# LoRa.net
KiCad netlist of a schematic drawn in Altium Designer
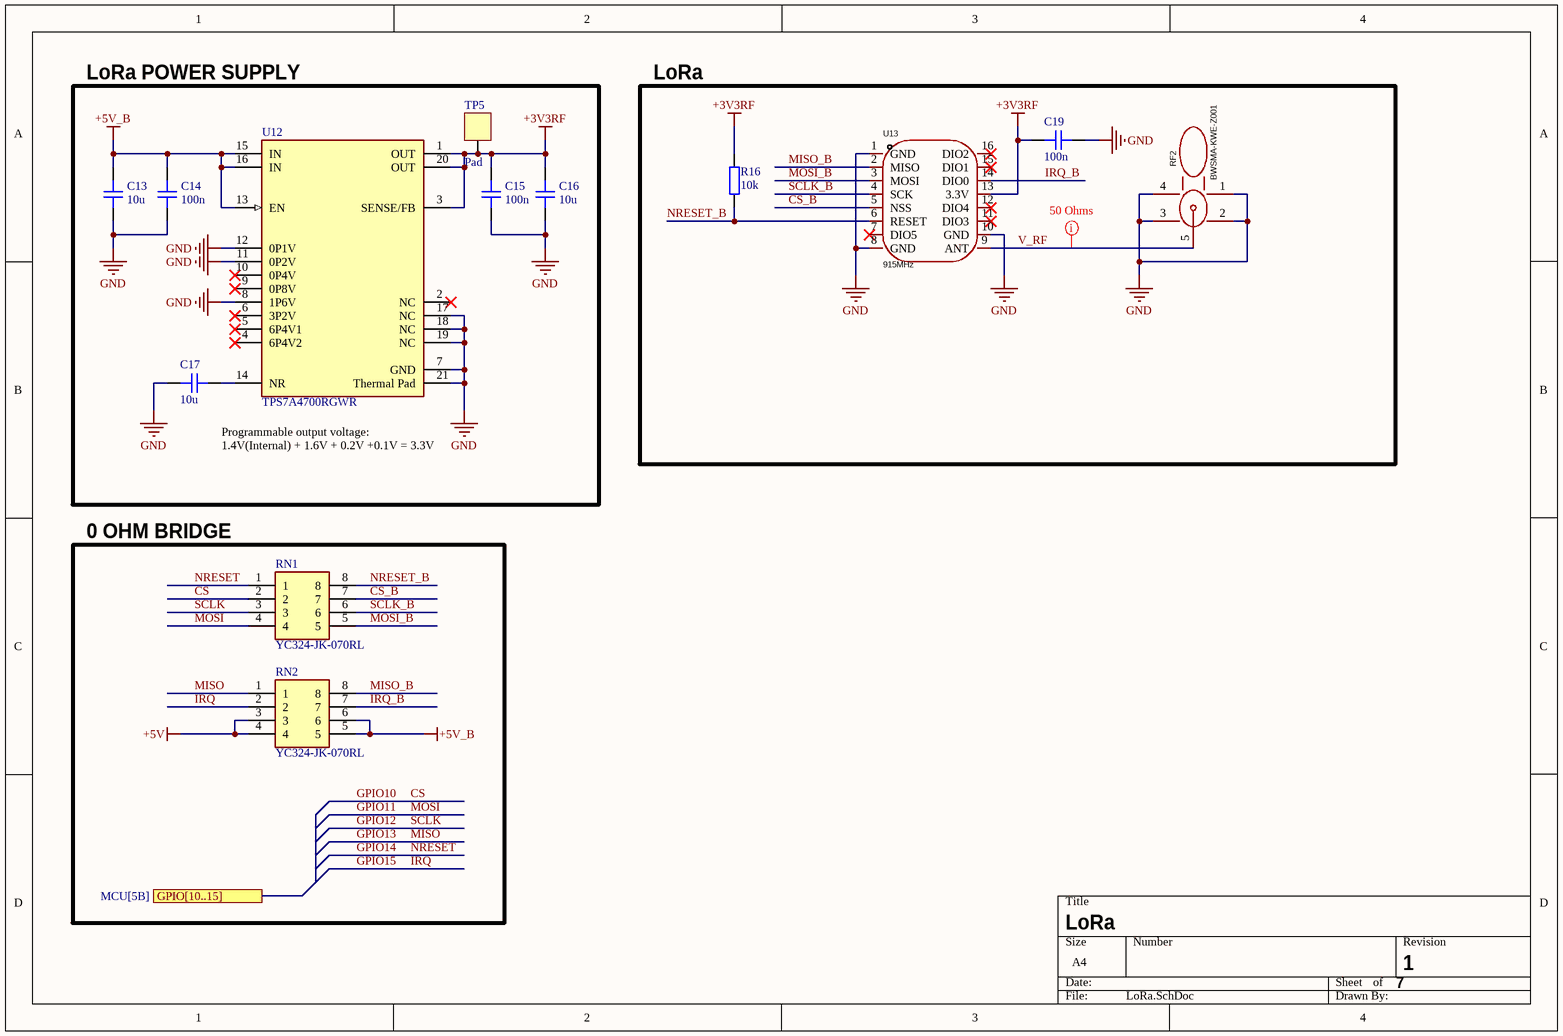
[diagram p0: LoRa.SchDoc]

(export (version "E")
  (design (tool "Eeschema 10.0.6"))
  (components
    (comp (ref "C13")
      (value "10u")
      (footprint "CAP_0402")
      (description "Capacitor SMD 0402")
      (fields (field (name "Comment") "CL05A106MQ5NUNC"))
      (libsource (lib "Schematic-Lib-PhilsLab") (part "CAP_0402"))
    )
    (comp (ref "C14")
      (value "CL05B104KB54PNC")
      (footprint "CAP_0402")
      (description "Capacitor SMD 0402")
      (fields (field (name "RATING") "100n"))
      (libsource (lib "Schematic-Lib-PhilsLab") (part "CAP_0402"))
    )
    (comp (ref "C15")
      (value "CL05B104KB54PNC")
      (footprint "CAP_0402")
      (description "Capacitor SMD 0402")
      (fields (field (name "RATING") "100n"))
      (libsource (lib "Schematic-Lib-PhilsLab") (part "CAP_0402"))
    )
    (comp (ref "C16")
      (value "10u")
      (footprint "CAP_0402")
      (description "Capacitor SMD 0402")
      (fields (field (name "Comment") "CL05A106MQ5NUNC"))
      (libsource (lib "Schematic-Lib-PhilsLab") (part "CAP_0402"))
    )
    (comp (ref "C17")
      (value "10u")
      (footprint "CAP_0402")
      (description "Capacitor SMD 0402")
      (fields (field (name "Comment") "CL05A106MQ5NUNC"))
      (libsource (lib "Schematic-Lib-PhilsLab") (part "CAP_0402"))
    )
    (comp (ref "C19")
      (value "CL05B104KB54PNC")
      (footprint "CAP_0402")
      (description "Capacitor SMD 0402")
      (fields (field (name "RATING") "100n"))
      (libsource (lib "Schematic-Lib-PhilsLab") (part "CAP_0402"))
    )
    (comp (ref "R16")
      (value "10k")
      (footprint "RES_0402")
      (description "Resistor SMD 0402")
      (fields (field (name "Comment") "0402WGF1002TCE"))
      (libsource (lib "Schematic-Lib-PhilsLab") (part "RES_0402"))
    )
    (comp (ref "RF2")
      (value "BWSMA-KWE-Z001")
      (footprint "SMA-TH_BWSMA-KWE-Z001")
      (fields (field (name "MANUFACTURER") "BAT WIRELESS(蝙蝠无线)"))
      (libsource (lib "JLCPCB_parts_library") (part "BWSMA-KWE-Z001"))
    )
    (comp (ref "RN1")
      (value "YC324-JK-070RL")
      (footprint "JLCPCB_parts_library:YC324JK07220RL")
      (description "Resistor Network")
      (fields (field (name "MOUSER PART NUMBER") "603-YC324-JK-070RL"))
      (libsource (lib "JLCPCB_parts_library") (part "YC324-JK-070RL"))
    )
    (comp (ref "RN2")
      (value "YC324-JK-070RL")
      (footprint "JLCPCB_parts_library:YC324JK07220RL")
      (description "Resistor Network")
      (fields (field (name "MOUSER PART NUMBER") "603-YC324-JK-070RL"))
      (libsource (lib "JLCPCB_parts_library") (part "YC324-JK-070RL"))
    )
    (comp (ref "TP5")
      (value "Pad")
      (footprint "PAD_SQ_2MM")
      (description "Test Point Square 2mm")
      (libsource (lib "Schematic-Lib-PhilsLab") (part "PAD_SQ_2MM"))
    )
    (comp (ref "U12")
      (value "TPS7A4700RGWR")
      (footprint "FP-RGW0020A-MFG")
      (description "IC REG LINEAR POS ADJ 1A 20VQFN")
      (fields
        (field (name "OCTOPART") "https://octopart.com/tps7a4700rgwr-texas+instruments-21221956")
        (field (name "MANUFACTURER") "Texas Instruments")
      )
      (libsource (lib "Altium Content Vault") (part "8e99b082ac9f85253ef2256b190b767"))
    )
    (comp (ref "U13")
      (value "915MHz")
      (footprint "LCC-16_L16.0-W16.0-P2.00-TL")
      (fields
        (field (name "MANUFACTURER") "DreamLNK(骏晔科技)")
        (field (name "MANUFACTURER PART") "DL-RFM95-915M")
      )
      (libsource (lib "JLCPCB_parts_library") (part "DL-RFM95-915M"))
    )
  )
  (nets
    (net (code "1") (name "+3V3RF") (class "Default")
      (node (ref "C15") (pin "2") (pinfunction "2_2") (pintype "passive"))
      (node (ref "C16") (pin "2") (pinfunction "2_2") (pintype "passive"))
      (node (ref "C19") (pin "2") (pinfunction "2_2") (pintype "passive"))
      (node (ref "R16") (pin "1") (pinfunction "1_1") (pintype "passive"))
      (node (ref "TP5") (pin "1") (pinfunction "1_1") (pintype "passive"))
      (node (ref "U12") (pin "1") (pinfunction "OUT_1") (pintype "power_in"))
      (node (ref "U12") (pin "20") (pinfunction "OUT_20") (pintype "power_in"))
      (node (ref "U12") (pin "3") (pinfunction "SENSE/FB_3") (pintype "passive"))
      (node (ref "U13") (pin "13") (pinfunction "3.3V_13") (pintype "passive"))
    )
    (net (code "2") (name "+5V") (class "Default")
      (node (ref "RN2") (pin "3") (pinfunction "3_3") (pintype "passive"))
      (node (ref "RN2") (pin "4") (pinfunction "4_4") (pintype "passive"))
    )
    (net (code "3") (name "+5V_B") (class "Default")
      (node (ref "C13") (pin "2") (pinfunction "2_2") (pintype "passive"))
      (node (ref "C14") (pin "2") (pinfunction "2_2") (pintype "passive"))
      (node (ref "RN2") (pin "5") (pinfunction "5_5") (pintype "passive"))
      (node (ref "RN2") (pin "6") (pinfunction "6_6") (pintype "passive"))
      (node (ref "U12") (pin "13") (pinfunction "EN_13") (pintype "input"))
      (node (ref "U12") (pin "15") (pinfunction "IN_15") (pintype "power_in"))
      (node (ref "U12") (pin "16") (pinfunction "IN_16") (pintype "power_in"))
    )
    (net (code "4") (name "/CS_B") (class "Default")
      (node (ref "RN1") (pin "7") (pinfunction "7_7") (pintype "passive"))
      (node (ref "U13") (pin "5") (pinfunction "NSS_5") (pintype "passive"))
    )
    (net (code "5") (name "/GPIO10") (class "Default")
      (node (ref "RN1") (pin "2") (pinfunction "2_2") (pintype "passive"))
    )
    (net (code "6") (name "/GPIO11") (class "Default")
      (node (ref "RN1") (pin "4") (pinfunction "4_4") (pintype "passive"))
    )
    (net (code "7") (name "/GPIO12") (class "Default")
      (node (ref "RN1") (pin "3") (pinfunction "3_3") (pintype "passive"))
    )
    (net (code "8") (name "/GPIO13") (class "Default")
      (node (ref "RN2") (pin "1") (pinfunction "1_1") (pintype "passive"))
    )
    (net (code "9") (name "/GPIO14") (class "Default")
      (node (ref "RN1") (pin "1") (pinfunction "1_1") (pintype "passive"))
    )
    (net (code "10") (name "/GPIO15") (class "Default")
      (node (ref "RN2") (pin "2") (pinfunction "2_2") (pintype "passive"))
    )
    (net (code "12") (name "/IRQ_B") (class "Default")
      (node (ref "RN2") (pin "7") (pinfunction "7_7") (pintype "passive"))
      (node (ref "U13") (pin "14") (pinfunction "DIO0_14") (pintype "passive"))
    )
    (net (code "13") (name "/MISO_B") (class "Default")
      (node (ref "RN2") (pin "8") (pinfunction "8_8") (pintype "passive"))
      (node (ref "U13") (pin "2") (pinfunction "MISO_2") (pintype "passive"))
    )
    (net (code "14") (name "/MOSI_B") (class "Default")
      (node (ref "RN1") (pin "5") (pinfunction "5_5") (pintype "passive"))
      (node (ref "U13") (pin "3") (pinfunction "MOSI_3") (pintype "passive"))
    )
    (net (code "15") (name "/NRESET_B") (class "Default")
      (node (ref "R16") (pin "2") (pinfunction "2_2") (pintype "passive"))
      (node (ref "RN1") (pin "8") (pinfunction "8_8") (pintype "passive"))
      (node (ref "U13") (pin "6") (pinfunction "RESET_6") (pintype "passive"))
    )
    (net (code "16") (name "/SCLK_B") (class "Default")
      (node (ref "RN1") (pin "6") (pinfunction "6_6") (pintype "passive"))
      (node (ref "U13") (pin "4") (pinfunction "SCK_4") (pintype "passive"))
    )
    (net (code "17") (name "/V_RF") (class "Default")
      (node (ref "RF2") (pin "5") (pinfunction "5_5") (pintype "passive"))
      (node (ref "U13") (pin "9") (pinfunction "ANT_9") (pintype "passive"))
    )
    (net (code "18") (name "GND") (class "Default")
      (node (ref "C13") (pin "1") (pinfunction "1_1") (pintype "passive"))
      (node (ref "C14") (pin "1") (pinfunction "1_1") (pintype "passive"))
      (node (ref "C15") (pin "1") (pinfunction "1_1") (pintype "passive"))
      (node (ref "C16") (pin "1") (pinfunction "1_1") (pintype "passive"))
      (node (ref "C17") (pin "2") (pinfunction "2_2") (pintype "passive"))
      (node (ref "C19") (pin "1") (pinfunction "1_1") (pintype "passive"))
      (node (ref "RF2") (pin "1") (pinfunction "1_1") (pintype "passive"))
      (node (ref "RF2") (pin "2") (pinfunction "2_2") (pintype "passive"))
      (node (ref "RF2") (pin "3") (pinfunction "3_3") (pintype "passive"))
      (node (ref "RF2") (pin "4") (pinfunction "4_4") (pintype "passive"))
      (node (ref "U12") (pin "11") (pinfunction "0P2V_11") (pintype "passive"))
      (node (ref "U12") (pin "12") (pinfunction "0P1V_12") (pintype "passive"))
      (node (ref "U12") (pin "17") (pinfunction "NC_17") (pintype "passive"))
      (node (ref "U12") (pin "18") (pinfunction "NC_18") (pintype "passive"))
      (node (ref "U12") (pin "19") (pinfunction "NC_19") (pintype "passive"))
      (node (ref "U12") (pin "21") (pinfunction "Thermal_Pad_21") (pintype "power_in"))
      (node (ref "U12") (pin "7") (pinfunction "GND_7") (pintype "power_in"))
      (node (ref "U12") (pin "8") (pinfunction "1P6V_8") (pintype "passive"))
      (node (ref "U13") (pin "1") (pinfunction "GND_1") (pintype "passive"))
      (node (ref "U13") (pin "10") (pinfunction "GND_10") (pintype "passive"))
      (node (ref "U13") (pin "8") (pinfunction "GND_8") (pintype "passive"))
    )
    (net (code "19") (name "Net-(U12-NR)") (class "Default")
      (node (ref "C17") (pin "1") (pinfunction "1_1") (pintype "passive"))
      (node (ref "U12") (pin "14") (pinfunction "NR_14") (pintype "passive"))
    )
    (net (code "20") (name "unconnected-(U12-0P4V-Pad10)") (class "Default")
      (node (ref "U12") (pin "10") (pinfunction "0P4V_10") (pintype "passive+no_connect"))
    )
    (net (code "21") (name "unconnected-(U12-0P8V-Pad9)") (class "Default")
      (node (ref "U12") (pin "9") (pinfunction "0P8V_9") (pintype "passive+no_connect"))
    )
    (net (code "22") (name "unconnected-(U12-3P2V-Pad6)") (class "Default")
      (node (ref "U12") (pin "6") (pinfunction "3P2V_6") (pintype "passive+no_connect"))
    )
    (net (code "23") (name "unconnected-(U12-6P4V1-Pad5)") (class "Default")
      (node (ref "U12") (pin "5") (pinfunction "6P4V1_5") (pintype "passive+no_connect"))
    )
    (net (code "24") (name "unconnected-(U12-6P4V2-Pad4)") (class "Default")
      (node (ref "U12") (pin "4") (pinfunction "6P4V2_4") (pintype "passive+no_connect"))
    )
    (net (code "25") (name "unconnected-(U12-NC-Pad2)") (class "Default")
      (node (ref "U12") (pin "2") (pinfunction "NC_2") (pintype "passive+no_connect"))
    )
    (net (code "26") (name "unconnected-(U13-DIO1-Pad15)") (class "Default")
      (node (ref "U13") (pin "15") (pinfunction "DIO1_15") (pintype "passive+no_connect"))
    )
    (net (code "27") (name "unconnected-(U13-DIO2-Pad16)") (class "Default")
      (node (ref "U13") (pin "16") (pinfunction "DIO2_16") (pintype "passive+no_connect"))
    )
    (net (code "28") (name "unconnected-(U13-DIO3-Pad11)") (class "Default")
      (node (ref "U13") (pin "11") (pinfunction "DIO3_11") (pintype "passive+no_connect"))
    )
    (net (code "29") (name "unconnected-(U13-DIO4-Pad12)") (class "Default")
      (node (ref "U13") (pin "12") (pinfunction "DIO4_12") (pintype "passive+no_connect"))
    )
    (net (code "30") (name "unconnected-(U13-DIO5-Pad7)") (class "Default")
      (node (ref "U13") (pin "7") (pinfunction "DIO5_7") (pintype "passive+no_connect"))
    )
  )
)
